# Artemis-MicroMod.net
KiCad netlist of a schematic drawn in EAGLE
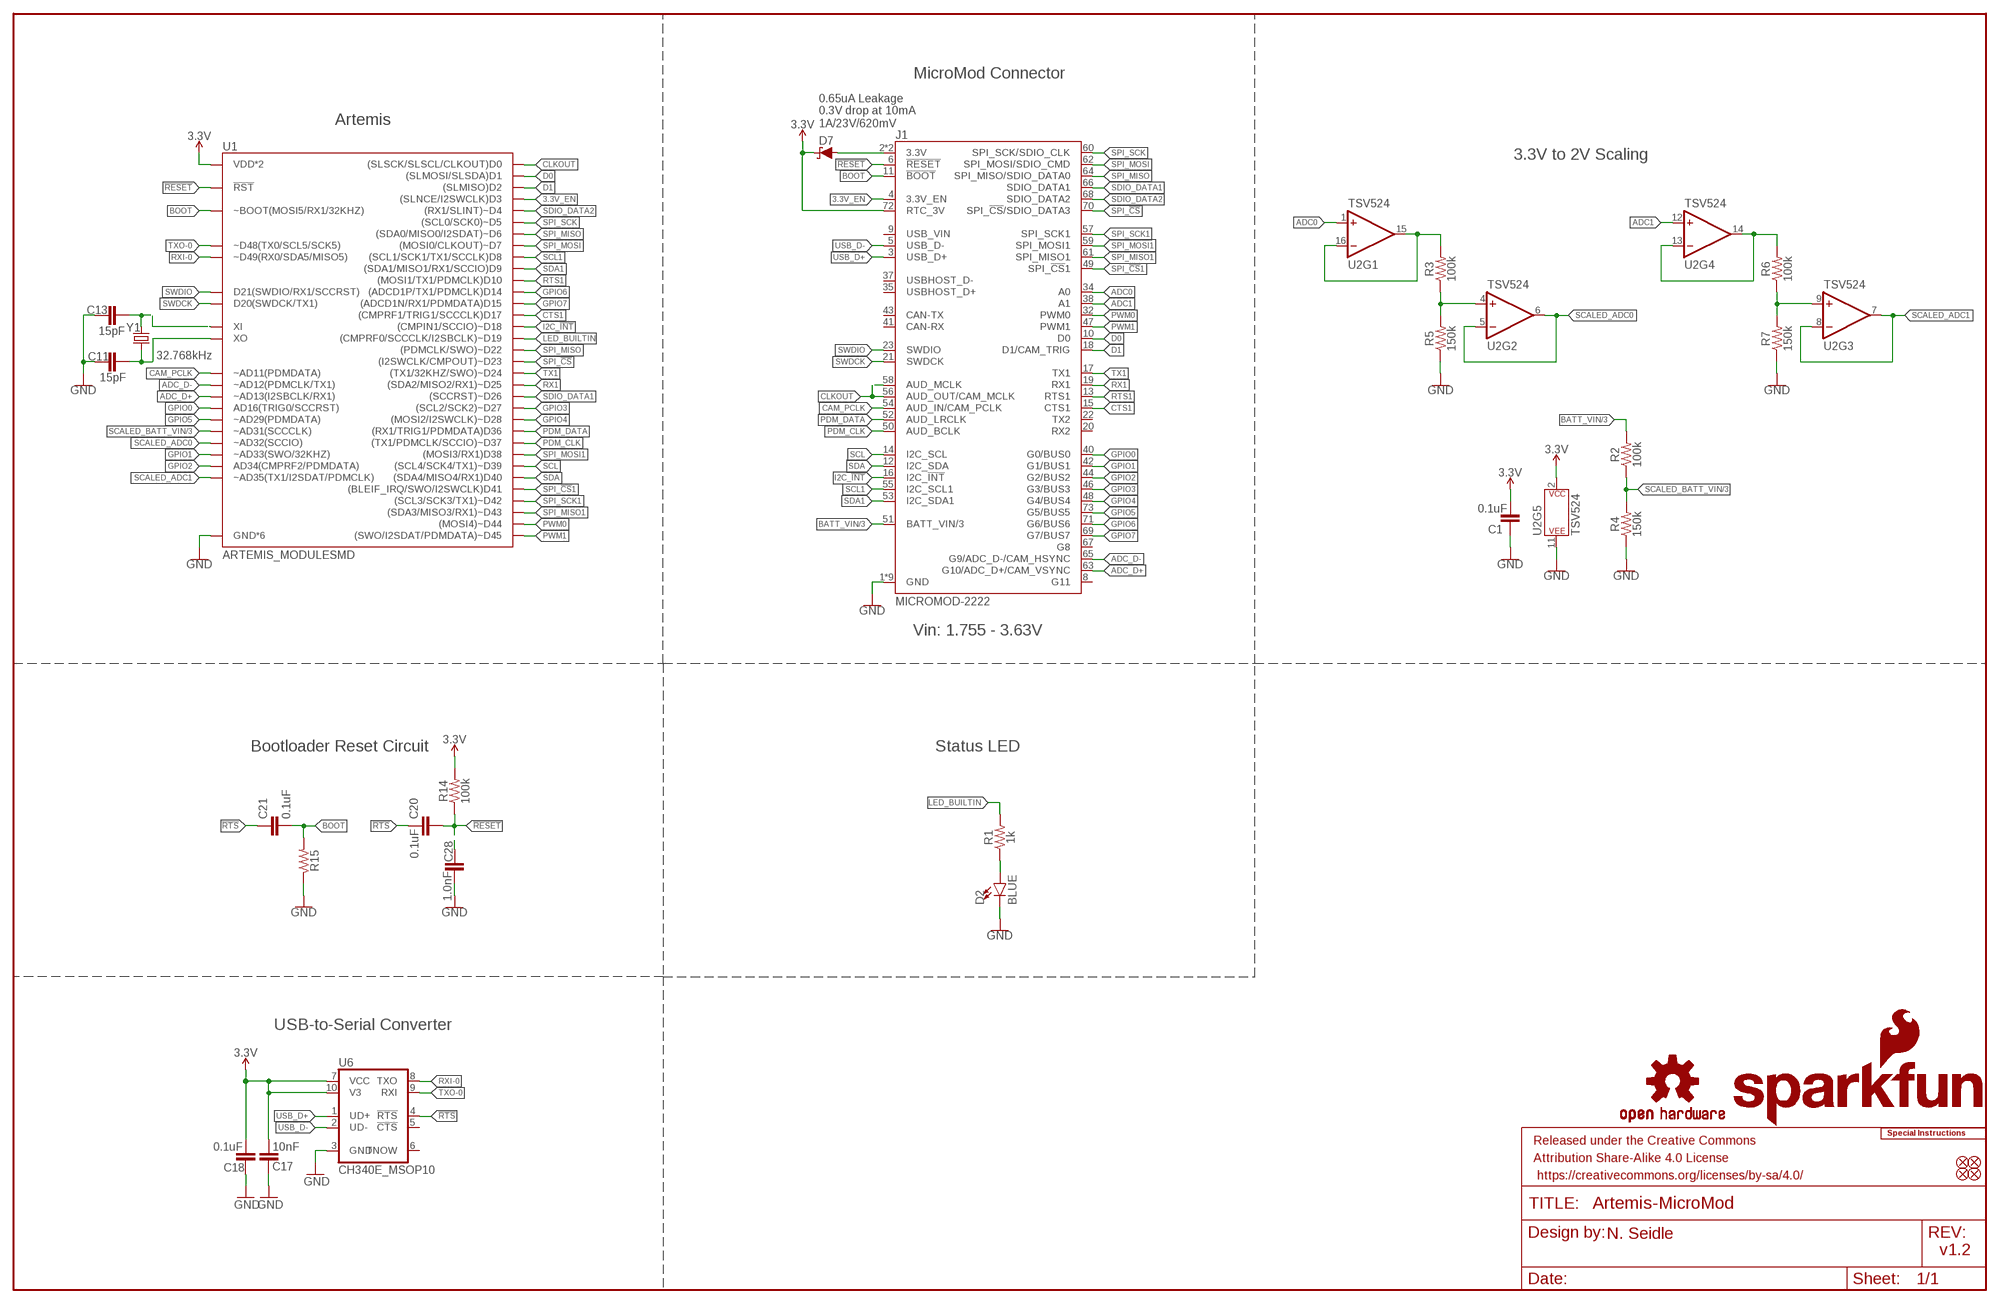
[diagram p0: schematic, sheet 1]

(export (version "E")
  (design (tool "Eeschema 10.0.6"))
  (components
    (comp (ref "C1")
      (value "0.1uF")
      (footprint "eagle-import:0402-TIGHT")
      (libsource (lib "eagle-import") (part "0.1UF-0402T-16V-10%"))
    )
    (comp (ref "C11")
      (value "15pF")
      (footprint "eagle-import:0402-TIGHT")
      (libsource (lib "eagle-import") (part "15PF-0402T-50V-5%"))
    )
    (comp (ref "C13")
      (value "15pF")
      (footprint "eagle-import:0402-TIGHT")
      (libsource (lib "eagle-import") (part "15PF-0402T-50V-5%"))
    )
    (comp (ref "C17")
      (value "10nF")
      (footprint "eagle-import:0402-TIGHT")
      (libsource (lib "eagle-import") (part "10NF-0402T-25V-10%"))
    )
    (comp (ref "C18")
      (value "0.1uF")
      (footprint "eagle-import:0402-TIGHT")
      (libsource (lib "eagle-import") (part "0.1UF-0402T-16V-10%"))
    )
    (comp (ref "C20")
      (value "0.1uF")
      (footprint "eagle-import:0402-TIGHT")
      (libsource (lib "eagle-import") (part "0.1UF-0402T-16V-10%"))
    )
    (comp (ref "C21")
      (value "0.1uF")
      (footprint "eagle-import:0402-TIGHT")
      (libsource (lib "eagle-import") (part "0.1UF-0402T-16V-10%"))
    )
    (comp (ref "C28")
      (value "1.0nF")
      (footprint "eagle-import:0402-TIGHT")
      (libsource (lib "eagle-import") (part "1.0NF/1000PF-0402_TIGHT-50V-10%"))
    )
    (comp (ref "D2")
      (value "BLUE")
      (footprint "eagle-import:LED-0603")
      (libsource (lib "eagle-import") (part "LED-BLUE0603"))
    )
    (comp (ref "D7")
      (value "1A/23V/620mV")
      (footprint "eagle-import:SOD-323")
      (libsource (lib "eagle-import") (part "DIODE-SCHOTTKY-BAT20J"))
    )
    (comp (ref "FD1")
      (value "FIDUCIALUFIDUCIAL")
      (footprint "eagle-import:FIDUCIAL-MICRO")
      (libsource (lib "eagle-import") (part "FIDUCIALUFIDUCIAL"))
    )
    (comp (ref "FD2")
      (value "FIDUCIALUFIDUCIAL")
      (footprint "eagle-import:FIDUCIAL-MICRO")
      (libsource (lib "eagle-import") (part "FIDUCIALUFIDUCIAL"))
    )
    (comp (ref "FD3")
      (value "FIDUCIALUFIDUCIAL")
      (footprint "eagle-import:FIDUCIAL-MICRO")
      (libsource (lib "eagle-import") (part "FIDUCIALUFIDUCIAL"))
    )
    (comp (ref "FD4")
      (value "FIDUCIALUFIDUCIAL")
      (footprint "eagle-import:FIDUCIAL-MICRO")
      (libsource (lib "eagle-import") (part "FIDUCIALUFIDUCIAL"))
    )
    (comp (ref "FRAME1")
      (value "FRAME-LEDGER")
      (footprint "eagle-import:CREATIVE_COMMONS")
      (libsource (lib "eagle-import") (part "FRAME-LEDGER"))
    )
    (comp (ref "J1")
      (value "MICROMOD-2222")
      (footprint "eagle-import:M.2-CARD-E-22")
      (libsource (lib "eagle-import") (part "MICROMOD-2222"))
    )
    (comp (ref "LOGO1")
      (value "SFE_LOGO_NAME_FLAME.1_INCH")
      (footprint "eagle-import:SFE_LOGO_NAME_FLAME_.1")
      (libsource (lib "eagle-import") (part "SFE_LOGO_NAME_FLAME.1_INCH"))
    )
    (comp (ref "LOGO2")
      (value "SFE_LOGO_FLAME.1_INCH")
      (footprint "eagle-import:SFE_LOGO_FLAME_.1")
      (libsource (lib "eagle-import") (part "SFE_LOGO_FLAME.1_INCH"))
    )
    (comp (ref "LOGO3")
      (value "OSHW-LOGOMINI")
      (footprint "eagle-import:OSHW-LOGO-MINI")
      (libsource (lib "eagle-import") (part "OSHW-LOGOMINI"))
    )
    (comp (ref "LOGO4")
      (value "SPECIAL_INSTRUCTIONS-ORDERING")
      (footprint "eagle-import:ORDERING_INSTRUCTIONS")
      (libsource (lib "eagle-import") (part "SPECIAL_INSTRUCTIONS-ORDERING"))
    )
    (comp (ref "R1")
      (value "1k")
      (footprint "eagle-import:0402-TIGHT")
      (libsource (lib "eagle-import") (part "1KOHM-0402T-1/16W-1%"))
    )
    (comp (ref "R2")
      (value "100k")
      (footprint "eagle-import:0402-TIGHT")
      (libsource (lib "eagle-import") (part "100KOHM-0402T-1/16W-1%"))
    )
    (comp (ref "R3")
      (value "100k")
      (footprint "eagle-import:0402-TIGHT")
      (libsource (lib "eagle-import") (part "100KOHM-0402T-1/16W-1%"))
    )
    (comp (ref "R4")
      (value "150k")
      (footprint "eagle-import:0402-TIGHT")
      (libsource (lib "eagle-import") (part "150KOHM-0402T-1/16W-1%"))
    )
    (comp (ref "R5")
      (value "150k")
      (footprint "eagle-import:0402-TIGHT")
      (libsource (lib "eagle-import") (part "150KOHM-0402T-1/16W-1%"))
    )
    (comp (ref "R6")
      (value "100k")
      (footprint "eagle-import:0402-TIGHT")
      (libsource (lib "eagle-import") (part "100KOHM-0402T-1/16W-1%"))
    )
    (comp (ref "R7")
      (value "150k")
      (footprint "eagle-import:0402-TIGHT")
      (libsource (lib "eagle-import") (part "150KOHM-0402T-1/16W-1%"))
    )
    (comp (ref "R14")
      (value "100k")
      (footprint "eagle-import:0402-TIGHT")
      (libsource (lib "eagle-import") (part "100KOHM-0402T-1/16W-1%"))
    )
    (comp (ref "R15")
      (value "220KOHM-0402T-1/16W-1%")
      (footprint "eagle-import:0402-TIGHT")
      (libsource (lib "eagle-import") (part "220KOHM-0402T-1/16W-1%"))
    )
    (comp (ref "U1")
      (value "ARTEMIS_MODULESMD")
      (footprint "eagle-import:ARTEMIS_FP")
      (libsource (lib "eagle-import") (part "ARTEMIS_MODULESMD"))
    )
    (comp (ref "U2")
      (value "TSV524")
      (footprint "eagle-import:QFN-16")
      (libsource (lib "eagle-import") (part "TSV524"))
    )
    (comp (ref "U6")
      (value "CH340E_MSOP10")
      (footprint "eagle-import:MSOP10")
      (libsource (lib "eagle-import") (part "CH340E_MSOP10"))
    )
    (comp (ref "Y1")
      (value "32.768kHz")
      (footprint "eagle-import:CRYSTAL-SMD-3.2X1.5MM")
      (libsource (lib "eagle-import") (part "CRYSTAL-32.768KHZSMD-3.2X1.5"))
    )
  )
  (nets
    (net (code "1") (name "/I2C_~{INT}") (class "Default")
      (node (ref "J1") (pin "16") (pinfunction "I2C_~{INT}_16") (pintype "bidirectional"))
      (node (ref "U1") (pin "~D18") (pinfunction "(CMPIN1/SCCIO)~{D18}_~D18") (pintype "bidirectional"))
    )
    (net (code "2") (name "/SPI_~{CS}") (class "Default")
      (node (ref "J1") (pin "70") (pinfunction "SPI_~{CS}/SDIO_DATA3_70") (pintype "bidirectional"))
      (node (ref "U1") (pin "~D23") (pinfunction "(I2SWCLK/CMPOUT)~{D23}_~D23") (pintype "bidirectional"))
    )
    (net (code "3") (name "/SPI_~{CS}1") (class "Default")
      (node (ref "J1") (pin "49") (pinfunction "SPI_~{CS}1_49") (pintype "bidirectional"))
      (node (ref "U1") (pin "D41") (pinfunction "(BLEIF_IRQ/SWO/I2SWCLK)D41_D41") (pintype "bidirectional"))
    )
    (net (code "4") (name "/~{RESET}") (class "Default")
      (node (ref "C20") (pin "2") (pinfunction "2_2") (pintype "passive"))
      (node (ref "C28") (pin "1") (pinfunction "1_1") (pintype "passive"))
      (node (ref "J1") (pin "6") (pinfunction "~{RESET}_6") (pintype "bidirectional"))
      (node (ref "R14") (pin "1") (pinfunction "1_1") (pintype "passive"))
      (node (ref "U1") (pin "~RST") (pinfunction "~{RST}_~RST") (pintype "bidirectional"))
    )
    (net (code "5") (name "/~{RTS}") (class "Default")
      (node (ref "C20") (pin "1") (pinfunction "1_1") (pintype "passive"))
      (node (ref "C21") (pin "1") (pinfunction "1_1") (pintype "passive"))
      (node (ref "U6") (pin "4") (pinfunction "~{RTS}_4") (pintype "bidirectional"))
    )
    (net (code "6") (name "3.3V") (class "Default")
      (node (ref "C1") (pin "1") (pinfunction "1_1") (pintype "passive"))
      (node (ref "C17") (pin "1") (pinfunction "1_1") (pintype "passive"))
      (node (ref "C18") (pin "1") (pinfunction "1_1") (pintype "passive"))
      (node (ref "D7") (pin "C") (pinfunction "C_C") (pintype "passive"))
      (node (ref "J1") (pin "72") (pinfunction "RTC_3V_72") (pintype "bidirectional"))
      (node (ref "R14") (pin "2") (pinfunction "2_2") (pintype "passive"))
      (node (ref "U1") (pin "VDD@36") (pinfunction "VDD*2_VDD@36") (pintype "bidirectional"))
      (node (ref "U1") (pin "VDD@37") (pinfunction "VDD*2_VDD@37") (pintype "bidirectional"))
      (node (ref "U2") (pin "2") (pinfunction "V+_2") (pintype "bidirectional"))
      (node (ref "U6") (pin "10") (pinfunction "V3_10") (pintype "bidirectional"))
      (node (ref "U6") (pin "7") (pinfunction "VCC_7") (pintype "bidirectional"))
    )
    (net (code "7") (name "3.3V_EN") (class "Default")
      (node (ref "J1") (pin "4") (pinfunction "3.3V_EN_4") (pintype "bidirectional"))
      (node (ref "U1") (pin "D3") (pinfunction "(SLNCE/I2SWCLK)D3_D3") (pintype "bidirectional"))
    )
    (net (code "8") (name "ADC0") (class "Default")
      (node (ref "J1") (pin "34") (pinfunction "A0_34") (pintype "bidirectional"))
      (node (ref "U2") (pin "1") (pinfunction "+IN_1") (pintype "input"))
    )
    (net (code "9") (name "ADC1") (class "Default")
      (node (ref "J1") (pin "38") (pinfunction "A1_38") (pintype "bidirectional"))
      (node (ref "U2") (pin "12") (pinfunction "+IN_12") (pintype "input"))
    )
    (net (code "10") (name "ADC_D+") (class "Default")
      (node (ref "J1") (pin "63") (pinfunction "G10/ADC_D+/CAM_VSYNC_63") (pintype "bidirectional"))
      (node (ref "U1") (pin "~AD13") (pinfunction "~{AD13(I2SBCLK/RX1})_~AD13") (pintype "bidirectional"))
    )
    (net (code "11") (name "ADC_D-") (class "Default")
      (node (ref "J1") (pin "65") (pinfunction "G9/ADC_D-/CAM_HSYNC_65") (pintype "bidirectional"))
      (node (ref "U1") (pin "~AD12") (pinfunction "~{AD12(PDMCLK/TX1})_~AD12") (pintype "bidirectional"))
    )
    (net (code "12") (name "BATT_VIN{slash}3") (class "Default")
      (node (ref "J1") (pin "51") (pinfunction "BATT_VIN/3_51") (pintype "bidirectional"))
      (node (ref "R2") (pin "2") (pinfunction "2_2") (pintype "passive"))
    )
    (net (code "13") (name "BOOT") (class "Default")
      (node (ref "C21") (pin "2") (pinfunction "2_2") (pintype "passive"))
      (node (ref "J1") (pin "11") (pinfunction "~{BOOT}_11") (pintype "bidirectional"))
      (node (ref "R15") (pin "2") (pinfunction "2_2") (pintype "passive"))
      (node (ref "U1") (pin "BOOT") (pinfunction "~{BOOT(MOSI5/RX1/32KHZ})_BOOT") (pintype "bidirectional"))
    )
    (net (code "14") (name "CAM_PCLK") (class "Default")
      (node (ref "J1") (pin "54") (pinfunction "AUD_IN/CAM_PCLK_54") (pintype "bidirectional"))
      (node (ref "U1") (pin "~AD11") (pinfunction "~{AD11(PDMDATA})_~AD11") (pintype "bidirectional"))
    )
    (net (code "15") (name "CLKOUT") (class "Default")
      (node (ref "J1") (pin "56") (pinfunction "AUD_OUT/CAM_MCLK_56") (pintype "bidirectional"))
      (node (ref "J1") (pin "58") (pinfunction "AUD_MCLK_58") (pintype "bidirectional"))
      (node (ref "U1") (pin "D0") (pinfunction "(SLSCK/SLSCL/CLKOUT)D0_D0") (pintype "bidirectional"))
    )
    (net (code "16") (name "CTS1") (class "Default")
      (node (ref "J1") (pin "15") (pinfunction "CTS1_15") (pintype "bidirectional"))
      (node (ref "U1") (pin "D17") (pinfunction "(CMPRF1/TRIG1/SCCCLK)D17_D17") (pintype "bidirectional"))
    )
    (net (code "17") (name "D0") (class "Default")
      (node (ref "J1") (pin "10") (pinfunction "D0_10") (pintype "bidirectional"))
      (node (ref "U1") (pin "D1") (pinfunction "(SLMOSI/SLSDA)D1_D1") (pintype "bidirectional"))
    )
    (net (code "18") (name "D1") (class "Default")
      (node (ref "J1") (pin "18") (pinfunction "D1/CAM_TRIG_18") (pintype "bidirectional"))
      (node (ref "U1") (pin "D2") (pinfunction "(SLMISO)D2_D2") (pintype "bidirectional"))
    )
    (net (code "19") (name "GND") (class "Default")
      (node (ref "C1") (pin "2") (pinfunction "2_2") (pintype "passive"))
      (node (ref "C11") (pin "1") (pinfunction "1_1") (pintype "passive"))
      (node (ref "C13") (pin "1") (pinfunction "1_1") (pintype "passive"))
      (node (ref "C17") (pin "2") (pinfunction "2_2") (pintype "passive"))
      (node (ref "C18") (pin "2") (pinfunction "2_2") (pintype "passive"))
      (node (ref "C28") (pin "2") (pinfunction "2_2") (pintype "passive"))
      (node (ref "D2") (pin "C") (pinfunction "C_C") (pintype "passive"))
      (node (ref "J1") (pin "1") (pinfunction "GND_1") (pintype "bidirectional"))
      (node (ref "J1") (pin "33") (pinfunction "GND_33") (pintype "bidirectional"))
      (node (ref "J1") (pin "36") (pinfunction "GND_36") (pintype "bidirectional"))
      (node (ref "J1") (pin "39") (pinfunction "GND_39") (pintype "bidirectional"))
      (node (ref "J1") (pin "45") (pinfunction "GND_45") (pintype "bidirectional"))
      (node (ref "J1") (pin "7") (pinfunction "GND_7") (pintype "bidirectional"))
      (node (ref "J1") (pin "75") (pinfunction "GND_75") (pintype "bidirectional"))
      (node (ref "J1") (pin "GND") (pinfunction "GND_GND") (pintype "bidirectional"))
      (node (ref "J1") (pin "GND-SM-B") (pinfunction "GND_GND-SM-B") (pintype "bidirectional"))
      (node (ref "R15") (pin "1") (pinfunction "1_1") (pintype "passive"))
      (node (ref "R4") (pin "1") (pinfunction "1_1") (pintype "passive"))
      (node (ref "R5") (pin "1") (pinfunction "1_1") (pintype "passive"))
      (node (ref "R7") (pin "1") (pinfunction "1_1") (pintype "passive"))
      (node (ref "U1") (pin "GND@1") (pinfunction "GND*6_GND@1") (pintype "bidirectional"))
      (node (ref "U1") (pin "GND@22") (pinfunction "GND*6_GND@22") (pintype "bidirectional"))
      (node (ref "U1") (pin "GND@38") (pinfunction "GND*6_GND@38") (pintype "bidirectional"))
      (node (ref "U1") (pin "GND@39") (pinfunction "GND*6_GND@39") (pintype "bidirectional"))
      (node (ref "U1") (pin "GND@47") (pinfunction "GND*6_GND@47") (pintype "bidirectional"))
      (node (ref "U1") (pin "GND@59") (pinfunction "GND*6_GND@59") (pintype "bidirectional"))
      (node (ref "U2") (pin "11") (pinfunction "V-_11") (pintype "bidirectional"))
      (node (ref "U6") (pin "3") (pinfunction "GND_3") (pintype "bidirectional"))
    )
    (net (code "20") (name "GPIO0") (class "Default")
      (node (ref "J1") (pin "40") (pinfunction "G0/BUS0_40") (pintype "bidirectional"))
      (node (ref "U1") (pin "AD16") (pinfunction "AD16(TRIG0/SCCRST)_AD16") (pintype "bidirectional"))
    )
    (net (code "21") (name "GPIO1") (class "Default")
      (node (ref "J1") (pin "42") (pinfunction "G1/BUS1_42") (pintype "bidirectional"))
      (node (ref "U1") (pin "~AD33/SWO") (pinfunction "~{AD33(SWO/32KHZ})_~AD33/SWO") (pintype "bidirectional"))
    )
    (net (code "22") (name "GPIO2") (class "Default")
      (node (ref "J1") (pin "44") (pinfunction "G2/BUS2_44") (pintype "bidirectional"))
      (node (ref "U1") (pin "AD34") (pinfunction "AD34(CMPRF2/PDMDATA)_AD34") (pintype "bidirectional"))
    )
    (net (code "23") (name "GPIO3") (class "Default")
      (node (ref "J1") (pin "46") (pinfunction "G3/BUS3_46") (pintype "bidirectional"))
      (node (ref "U1") (pin "~D27") (pinfunction "(SCL2/SCK2)~{D27}_~D27") (pintype "bidirectional"))
    )
    (net (code "24") (name "GPIO4") (class "Default")
      (node (ref "J1") (pin "48") (pinfunction "G4/BUS4_48") (pintype "bidirectional"))
      (node (ref "U1") (pin "~D28") (pinfunction "(MOSI2/I2SWCLK)~{D28}_~D28") (pintype "bidirectional"))
    )
    (net (code "25") (name "GPIO5") (class "Default")
      (node (ref "J1") (pin "73") (pinfunction "G5/BUS5_73") (pintype "bidirectional"))
      (node (ref "U1") (pin "~AD29") (pinfunction "~{AD29(PDMDATA})_~AD29") (pintype "bidirectional"))
    )
    (net (code "26") (name "GPIO6") (class "Default")
      (node (ref "J1") (pin "71") (pinfunction "G6/BUS6_71") (pintype "bidirectional"))
      (node (ref "U1") (pin "D14") (pinfunction "(ADCD1P/TX1/PDMCLK)D14_D14") (pintype "bidirectional"))
    )
    (net (code "27") (name "GPIO7") (class "Default")
      (node (ref "J1") (pin "69") (pinfunction "G7/BUS7_69") (pintype "bidirectional"))
      (node (ref "U1") (pin "D15") (pinfunction "(ADCD1N/RX1/PDMDATA)D15_D15") (pintype "bidirectional"))
    )
    (net (code "28") (name "LED_BUILTIN") (class "Default")
      (node (ref "R1") (pin "2") (pinfunction "2_2") (pintype "passive"))
      (node (ref "U1") (pin "~D19") (pinfunction "(CMPRF0/SCCCLK/I2SBCLK)~{D19}_~D19") (pintype "bidirectional"))
    )
    (net (code "29") (name "Net-(D2-PadA)") (class "Default")
      (node (ref "D2") (pin "A") (pinfunction "A_A") (pintype "passive"))
      (node (ref "R1") (pin "1") (pinfunction "1_1") (pintype "passive"))
    )
    (net (code "30") (name "Net-(D7-PadA)") (class "Default")
      (node (ref "D7") (pin "A") (pinfunction "A_A") (pintype "passive"))
      (node (ref "J1") (pin "2") (pinfunction "3.3V_2") (pintype "bidirectional"))
      (node (ref "J1") (pin "74") (pinfunction "3.3V_74") (pintype "bidirectional"))
    )
    (net (code "31") (name "Net-(U2A--IN)") (class "Default")
      (node (ref "R3") (pin "2") (pinfunction "2_2") (pintype "passive"))
      (node (ref "U2") (pin "15") (pinfunction "OUT_15") (pintype "output"))
      (node (ref "U2") (pin "16") (pinfunction "-IN_16") (pintype "input"))
    )
    (net (code "32") (name "Net-(U2B-+IN)") (class "Default")
      (node (ref "R3") (pin "1") (pinfunction "1_1") (pintype "passive"))
      (node (ref "R5") (pin "2") (pinfunction "2_2") (pintype "passive"))
      (node (ref "U2") (pin "4") (pinfunction "+IN_4") (pintype "input"))
    )
    (net (code "33") (name "Net-(U2C-+IN)") (class "Default")
      (node (ref "R6") (pin "1") (pinfunction "1_1") (pintype "passive"))
      (node (ref "R7") (pin "2") (pinfunction "2_2") (pintype "passive"))
      (node (ref "U2") (pin "9") (pinfunction "+IN_9") (pintype "input"))
    )
    (net (code "34") (name "Net-(U2D--IN)") (class "Default")
      (node (ref "R6") (pin "2") (pinfunction "2_2") (pintype "passive"))
      (node (ref "U2") (pin "13") (pinfunction "-IN_13") (pintype "input"))
      (node (ref "U2") (pin "14") (pinfunction "OUT_14") (pintype "output"))
    )
    (net (code "35") (name "Net-(Y1-1)") (class "Default")
      (node (ref "C13") (pin "2") (pinfunction "2_2") (pintype "passive"))
      (node (ref "Y1") (pin "P$1") (pinfunction "1_P$1") (pintype "passive"))
    )
    (net (code "36") (name "Net-(Y1-2)") (class "Default")
      (node (ref "C11") (pin "2") (pinfunction "2_2") (pintype "passive"))
      (node (ref "U1") (pin "XO") (pinfunction "XO_XO") (pintype "bidirectional"))
      (node (ref "Y1") (pin "P$2") (pinfunction "2_P$2") (pintype "passive"))
    )
    (net (code "37") (name "PDM_CLK") (class "Default")
      (node (ref "J1") (pin "50") (pinfunction "AUD_BCLK_50") (pintype "bidirectional"))
      (node (ref "U1") (pin "~D37") (pinfunction "(TX1/PDMCLK/SCCIO)~{D37}_~D37") (pintype "bidirectional"))
    )
    (net (code "38") (name "PDM_DATA") (class "Default")
      (node (ref "J1") (pin "52") (pinfunction "AUD_LRCLK_52") (pintype "bidirectional"))
      (node (ref "U1") (pin "D36") (pinfunction "(RX1/TRIG1/PDMDATA)D36_D36") (pintype "bidirectional"))
    )
    (net (code "39") (name "PWM0") (class "Default")
      (node (ref "J1") (pin "32") (pinfunction "PWM0_32") (pintype "bidirectional"))
      (node (ref "U1") (pin "~D44") (pinfunction "(MOSI4)~{D44}_~D44") (pintype "bidirectional"))
    )
    (net (code "40") (name "PWM1") (class "Default")
      (node (ref "J1") (pin "47") (pinfunction "PWM1_47") (pintype "bidirectional"))
      (node (ref "U1") (pin "~D45") (pinfunction "(SWO/I2SDAT/PDMDATA)~{D45}_~D45") (pintype "bidirectional"))
    )
    (net (code "41") (name "RTS1") (class "Default")
      (node (ref "J1") (pin "13") (pinfunction "RTS1_13") (pintype "bidirectional"))
      (node (ref "U1") (pin "D10") (pinfunction "(MOSI1/TX1/PDMCLK)D10_D10") (pintype "bidirectional"))
    )
    (net (code "42") (name "RX1") (class "Default")
      (node (ref "J1") (pin "19") (pinfunction "RX1_19") (pintype "bidirectional"))
      (node (ref "U1") (pin "~D25") (pinfunction "(SDA2/MISO2/RX1)~{D25}_~D25") (pintype "bidirectional"))
    )
    (net (code "43") (name "RXI-0") (class "Default")
      (node (ref "U1") (pin "RXI-0") (pinfunction "~{D49(RX0/SDA5/MISO5})_RXI-0") (pintype "bidirectional"))
      (node (ref "U6") (pin "8") (pinfunction "TXO_8") (pintype "bidirectional"))
    )
    (net (code "44") (name "SCALED_ADC0") (class "Default")
      (node (ref "U1") (pin "~AD32") (pinfunction "~{AD32(SCCIO})_~AD32") (pintype "bidirectional"))
      (node (ref "U2") (pin "5") (pinfunction "-IN_5") (pintype "input"))
      (node (ref "U2") (pin "6") (pinfunction "OUT_6") (pintype "output"))
    )
    (net (code "45") (name "SCALED_ADC1") (class "Default")
      (node (ref "U1") (pin "~AD35") (pinfunction "~{AD35(TX1/I2SDAT/PDMCLK})_~AD35") (pintype "bidirectional"))
      (node (ref "U2") (pin "7") (pinfunction "OUT_7") (pintype "output"))
      (node (ref "U2") (pin "8") (pinfunction "-IN_8") (pintype "input"))
    )
    (net (code "46") (name "SCALED_BATT_VIN{slash}3") (class "Default")
      (node (ref "R2") (pin "1") (pinfunction "1_1") (pintype "passive"))
      (node (ref "R4") (pin "2") (pinfunction "2_2") (pintype "passive"))
      (node (ref "U1") (pin "~AD31") (pinfunction "~{AD31(SCCCLK})_~AD31") (pintype "bidirectional"))
    )
    (net (code "47") (name "SCL") (class "Default")
      (node (ref "J1") (pin "14") (pinfunction "I2C_SCL_14") (pintype "bidirectional"))
      (node (ref "U1") (pin "~D39") (pinfunction "(SCL4/SCK4/TX1)~{D39}_~D39") (pintype "bidirectional"))
    )
    (net (code "48") (name "SCL1") (class "Default")
      (node (ref "J1") (pin "55") (pinfunction "I2C_SCL1_55") (pintype "bidirectional"))
      (node (ref "U1") (pin "D8") (pinfunction "(SCL1/SCK1/TX1/SCCLK)D8_D8") (pintype "bidirectional"))
    )
    (net (code "49") (name "SDA") (class "Default")
      (node (ref "J1") (pin "12") (pinfunction "I2C_SDA_12") (pintype "bidirectional"))
      (node (ref "U1") (pin "D40") (pinfunction "(SDA4/MISO4/RX1)D40_D40") (pintype "bidirectional"))
    )
    (net (code "50") (name "SDA1") (class "Default")
      (node (ref "J1") (pin "53") (pinfunction "I2C_SDA1_53") (pintype "bidirectional"))
      (node (ref "U1") (pin "D9") (pinfunction "(SDA1/MISO1/RX1/SCCIO)D9_D9") (pintype "bidirectional"))
    )
    (net (code "51") (name "SDIO_DATA1") (class "Default")
      (node (ref "J1") (pin "66") (pinfunction "SDIO_DATA1_66") (pintype "bidirectional"))
      (node (ref "U1") (pin "~D26") (pinfunction "(SCCRST)~{D26}_~D26") (pintype "bidirectional"))
    )
    (net (code "52") (name "SDIO_DATA2") (class "Default")
      (node (ref "J1") (pin "68") (pinfunction "SDIO_DATA2_68") (pintype "bidirectional"))
      (node (ref "U1") (pin "~D4") (pinfunction "(RX1/SLINT)~{D4}_~D4") (pintype "bidirectional"))
    )
    (net (code "53") (name "SPI_MISO") (class "Default")
      (node (ref "J1") (pin "64") (pinfunction "SPI_MISO/SDIO_DATA0_64") (pintype "bidirectional"))
      (node (ref "U1") (pin "~D22") (pinfunction "(PDMCLK/SWO)~{D22}_~D22") (pintype "bidirectional"))
      (node (ref "U1") (pin "~D6") (pinfunction "(SDA0/MISO0/I2SDAT)~{D6}_~D6") (pintype "bidirectional"))
    )
    (net (code "54") (name "SPI_MISO1") (class "Default")
      (node (ref "J1") (pin "61") (pinfunction "SPI_MISO1_61") (pintype "bidirectional"))
      (node (ref "U1") (pin "~D43") (pinfunction "(SDA3/MISO3/RX1)~{D43}_~D43") (pintype "bidirectional"))
    )
    (net (code "55") (name "SPI_MOSI") (class "Default")
      (node (ref "J1") (pin "62") (pinfunction "SPI_MOSI/SDIO_CMD_62") (pintype "bidirectional"))
      (node (ref "U1") (pin "D7") (pinfunction "(MOSI0/CLKOUT)~{D7}_D7") (pintype "bidirectional"))
    )
    (net (code "56") (name "SPI_MOSI1") (class "Default")
      (node (ref "J1") (pin "59") (pinfunction "SPI_MOSI1_59") (pintype "bidirectional"))
      (node (ref "U1") (pin "D38") (pinfunction "(MOSI3/RX1)D38_D38") (pintype "bidirectional"))
    )
    (net (code "57") (name "SPI_SCK") (class "Default")
      (node (ref "J1") (pin "60") (pinfunction "SPI_SCK/SDIO_CLK_60") (pintype "bidirectional"))
      (node (ref "U1") (pin "~D5") (pinfunction "(SCL0/SCK0)~{D5}_~D5") (pintype "bidirectional"))
    )
    (net (code "58") (name "SPI_SCK1") (class "Default")
      (node (ref "J1") (pin "57") (pinfunction "SPI_SCK1_57") (pintype "bidirectional"))
      (node (ref "U1") (pin "~D42") (pinfunction "(SCL3/SCK3/TX1)~{D42}_~D42") (pintype "bidirectional"))
    )
    (net (code "59") (name "SWDCK") (class "Default")
      (node (ref "J1") (pin "21") (pinfunction "SWDCK_21") (pintype "bidirectional"))
      (node (ref "U1") (pin "SWDCK") (pinfunction "D20(SWDCK/TX1)_SWDCK") (pintype "bidirectional"))
    )
    (net (code "60") (name "SWDIO") (class "Default")
      (node (ref "J1") (pin "23") (pinfunction "SWDIO_23") (pintype "bidirectional"))
      (node (ref "U1") (pin "SWDIO") (pinfunction "D21(SWDIO/RX1/SCCRST)_SWDIO") (pintype "bidirectional"))
    )
    (net (code "61") (name "TX1") (class "Default")
      (node (ref "J1") (pin "17") (pinfunction "TX1_17") (pintype "bidirectional"))
      (node (ref "U1") (pin "~D24") (pinfunction "(TX1/32KHZ/SWO)~{D24}_~D24") (pintype "bidirectional"))
    )
    (net (code "62") (name "TXO-0") (class "Default")
      (node (ref "U1") (pin "TXO-0") (pinfunction "~{D48(TX0/SCL5/SCK5})_TXO-0") (pintype "bidirectional"))
      (node (ref "U6") (pin "9") (pinfunction "RXI_9") (pintype "bidirectional"))
    )
    (net (code "63") (name "USB_D+") (class "Default")
      (node (ref "J1") (pin "3") (pinfunction "USB_D+_3") (pintype "bidirectional"))
      (node (ref "U6") (pin "1") (pinfunction "UD+_1") (pintype "bidirectional"))
    )
    (net (code "64") (name "USB_D-") (class "Default")
      (node (ref "J1") (pin "5") (pinfunction "USB_D-_5") (pintype "bidirectional"))
      (node (ref "U6") (pin "2") (pinfunction "UD-_2") (pintype "bidirectional"))
    )
    (net (code "65") (name "unconnected-(J1-CAN-RX-Pad41)") (class "Default")
      (node (ref "J1") (pin "41") (pinfunction "CAN-RX_41") (pintype "bidirectional"))
    )
    (net (code "66") (name "unconnected-(J1-CAN-TX-Pad43)") (class "Default")
      (node (ref "J1") (pin "43") (pinfunction "CAN-TX_43") (pintype "bidirectional"))
    )
    (net (code "67") (name "unconnected-(J1-G8-Pad67)") (class "Default")
      (node (ref "J1") (pin "67") (pinfunction "G8_67") (pintype "bidirectional"))
    )
    (net (code "68") (name "unconnected-(J1-G11-Pad8)") (class "Default")
      (node (ref "J1") (pin "8") (pinfunction "G11_8") (pintype "bidirectional"))
    )
    (net (code "69") (name "unconnected-(J1-RX2-Pad20)") (class "Default")
      (node (ref "J1") (pin "20") (pinfunction "RX2_20") (pintype "bidirectional"))
    )
    (net (code "70") (name "unconnected-(J1-TX2-Pad22)") (class "Default")
      (node (ref "J1") (pin "22") (pinfunction "TX2_22") (pintype "bidirectional"))
    )
    (net (code "71") (name "unconnected-(J1-USBHOST_D+-Pad35)") (class "Default")
      (node (ref "J1") (pin "35") (pinfunction "USBHOST_D+_35") (pintype "bidirectional"))
    )
    (net (code "72") (name "unconnected-(J1-USBHOST_D--Pad37)") (class "Default")
      (node (ref "J1") (pin "37") (pinfunction "USBHOST_D-_37") (pintype "bidirectional"))
    )
    (net (code "73") (name "unconnected-(J1-USB_VIN-Pad9)") (class "Default")
      (node (ref "J1") (pin "9") (pinfunction "USB_VIN_9") (pintype "bidirectional"))
    )
    (net (code "74") (name "unconnected-(U1-PadXI)") (class "Default")
      (node (ref "U1") (pin "XI") (pinfunction "XI_XI") (pintype "bidirectional"))
    )
    (net (code "75") (name "unconnected-(U6-TNOW-Pad6)") (class "Default")
      (node (ref "U6") (pin "6") (pinfunction "TNOW_6") (pintype "bidirectional"))
    )
    (net (code "76") (name "unconnected-(U6-~{CTS}-Pad5)") (class "Default")
      (node (ref "U6") (pin "5") (pinfunction "~{CTS}_5") (pintype "bidirectional"))
    )
  )
)
